# MSP-ISO_Rev1_0.net
KiCad netlist of a schematic drawn in Altium Designer
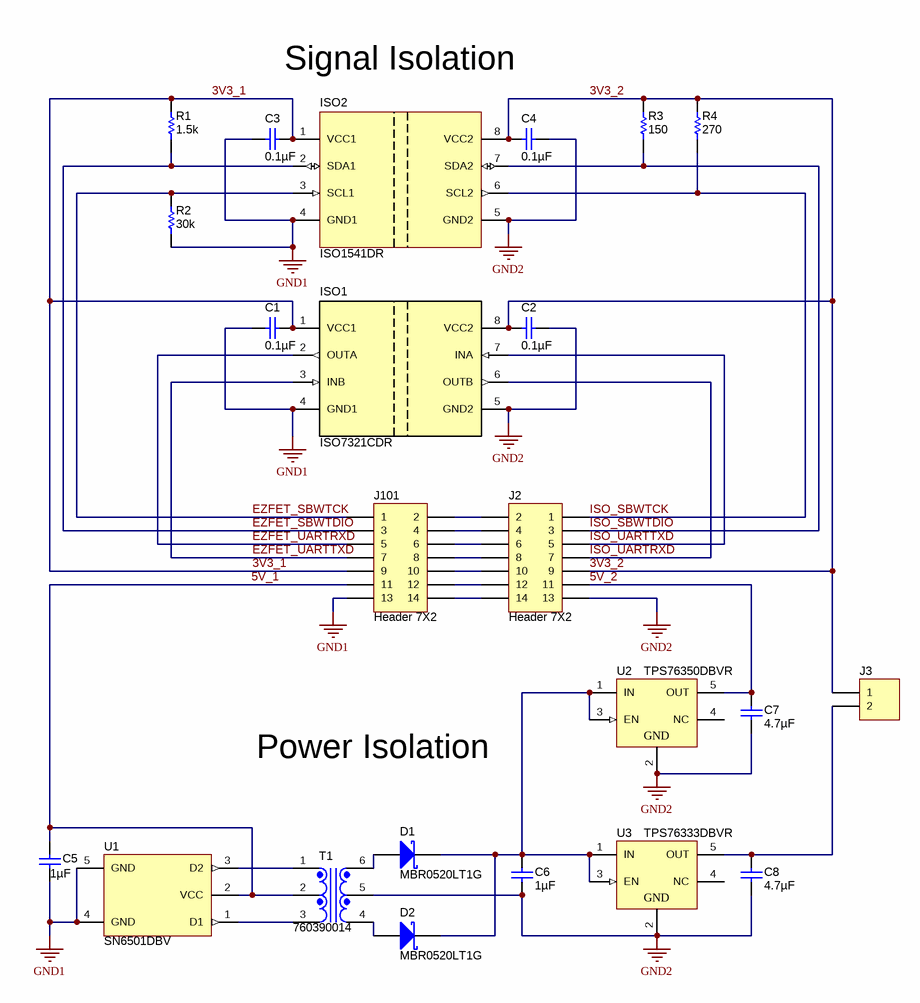
[diagram p0: MSP-ISO_Rev1_0.SchDoc]

(export (version "E")
  (design (tool "Eeschema 10.0.6"))
  (components
    (comp (ref "C1")
      (value "0603YC104JAT2A")
      (footprint "0603")
      (description "CAP, CERM, 0.1 µF, 16 V, +/- 5%, X7R, 0603")
      (fields
        (field (name "VALUEDISPLAYED") "0.1µF")
        (field (name "MANUFACTURER") "AVX")
        (field (name "PUBLISHER") "Texas Instruments")
      )
      (libsource (lib "Capacitor_Ceramic") (part "0603YC104JAT2A"))
    )
    (comp (ref "C2")
      (value "0603YC104JAT2A")
      (footprint "0603")
      (description "CAP, CERM, 0.1 µF, 16 V, +/- 5%, X7R, 0603")
      (fields
        (field (name "VALUEDISPLAYED") "0.1µF")
        (field (name "MANUFACTURER") "AVX")
        (field (name "PUBLISHER") "Texas Instruments")
      )
      (libsource (lib "Capacitor_Ceramic") (part "0603YC104JAT2A"))
    )
    (comp (ref "C3")
      (value "0603YC104JAT2A")
      (footprint "0603")
      (description "CAP, CERM, 0.1 µF, 16 V, +/- 5%, X7R, 0603")
      (fields
        (field (name "VALUEDISPLAYED") "0.1µF")
        (field (name "MANUFACTURER") "AVX")
        (field (name "PUBLISHER") "Texas Instruments")
      )
      (libsource (lib "Capacitor_Ceramic") (part "0603YC104JAT2A"))
    )
    (comp (ref "C4")
      (value "0603YC104JAT2A")
      (footprint "0603")
      (description "CAP, CERM, 0.1 µF, 16 V, +/- 5%, X7R, 0603")
      (fields
        (field (name "VALUEDISPLAYED") "0.1µF")
        (field (name "MANUFACTURER") "AVX")
        (field (name "PUBLISHER") "Texas Instruments")
      )
      (libsource (lib "Capacitor_Ceramic") (part "0603YC104JAT2A"))
    )
    (comp (ref "C5")
      (value "C1608X7R1C105K")
      (footprint "0603")
      (description "CAP, CERM, 1 µF, 16 V, +/- 10%, X7R, 0603")
      (fields
        (field (name "VALUEDISPLAYED") "1µF")
        (field (name "MANUFACTURER") "TDK")
        (field (name "PUBLISHER") "Texas Instruments")
      )
      (libsource (lib "Capacitor_Ceramic") (part "C1608X7R1C105K"))
    )
    (comp (ref "C6")
      (value "C1608X7R1C105K")
      (footprint "0603")
      (description "CAP, CERM, 1 µF, 16 V, +/- 10%, X7R, 0603")
      (fields
        (field (name "VALUEDISPLAYED") "1µF")
        (field (name "MANUFACTURER") "TDK")
        (field (name "PUBLISHER") "Texas Instruments")
      )
      (libsource (lib "Capacitor_Ceramic") (part "C1608X7R1C105K"))
    )
    (comp (ref "C7")
      (value "C1608X5R0J475M")
      (footprint "0603")
      (description "CAP, CERM, 4.7 µF, 6.3 V, +/- 20%, X5R, 0603")
      (fields
        (field (name "VALUEDISPLAYED") "4.7µF")
        (field (name "MANUFACTURER") "TDK")
        (field (name "PUBLISHER") "Texas Instruments")
      )
      (libsource (lib "Capacitor_Ceramic") (part "C1608X5R0J475M"))
    )
    (comp (ref "C8")
      (value "C1608X5R0J475M")
      (footprint "0603")
      (description "CAP, CERM, 4.7 µF, 6.3 V, +/- 20%, X5R, 0603")
      (fields
        (field (name "VALUEDISPLAYED") "4.7µF")
        (field (name "MANUFACTURER") "TDK")
        (field (name "PUBLISHER") "Texas Instruments")
      )
      (libsource (lib "Capacitor_Ceramic") (part "C1608X5R0J475M"))
    )
    (comp (ref "D1")
      (value "MBR0520LT1G")
      (footprint "SOD-123")
      (description "Diode, Schottky, 20 V, 0.5 A, SOD-123")
      (fields (field (name "MANUFACTURER") "ON Semiconductor") (field (name "PUBLISHER") "Texas Instruments"))
      (libsource (lib "Diode") (part "MBR0520LT1G"))
    )
    (comp (ref "D2")
      (value "MBR0520LT1G")
      (footprint "SOD-123")
      (description "Diode, Schottky, 20 V, 0.5 A, SOD-123")
      (fields (field (name "MANUFACTURER") "ON Semiconductor") (field (name "PUBLISHER") "Texas Instruments"))
      (libsource (lib "Diode") (part "MBR0520LT1G"))
    )
    (comp (ref "ISO1")
      (value "ISO7321CDR")
      (footprint "D0008B_N")
      (description "Robust EMC, Low Power, Dual-Channel Digital Isolators, D0008B")
      (fields
        (field (name "ALTERNATE PARTNUMBER") "ISO7321CD")
        (field (name "MANUFACTURER") "Texas Instruments")
        (field (name "SYMBOLCREATOR") "a0411947")
        (field (name "PUBLISHER") "Texas Instruments")
      )
      (libsource (lib "TI_Pre_Release1") (part "ISO7321CDR"))
    )
    (comp (ref "ISO2")
      (value "ISO1541DR")
      (footprint "D0008A_N")
      (description "Low-Power Bidirectional I2C Isolators, D0008A")
      (fields
        (field (name "ALTERNATE PARTNUMBER") "ISO1541D")
        (field (name "MANUFACTURER") "Texas Instruments")
        (field (name "SYMBOLCREATOR") "a0411947")
        (field (name "PUBLISHER") "Texas Instruments")
      )
      (libsource (lib "TI_Pre_Release1") (part "ISO1541DR"))
    )
    (comp (ref "J2")
      (value "Header 7X2")
      (footprint "HDR2X7")
      (description "Header, 7-Pin, Dual row")
      (fields (field (name "PUBLISHER") "Altium Limited"))
      (libsource (lib "Miscellaneous Connectors") (part "Header 7X2"))
    )
    (comp (ref "J3")
      (value "Supply_components")
      (footprint "HDR1X2")
      (description "Header, 2-Pin")
      (fields (field (name "PUBLISHER") "Altium Limited"))
      (libsource (lib "Miscellaneous Connectors") (part "Header 2"))
    )
    (comp (ref "J101")
      (value "Header 7X2")
      (footprint "HDR2X7")
      (description "Header, 7-Pin, Dual row")
      (fields (field (name "PUBLISHER") "Altium Limited"))
      (libsource (lib "") (part "Header 7X2_1"))
    )
    (comp (ref "R1")
      (value "CRCW04021K50JNED")
      (footprint "0402")
      (description "RES, 1.5 k, 5%, 0.063 W, 0402")
      (fields
        (field (name "VALUEDISPLAYED") "1.5k")
        (field (name "MANUFACTURER") "Vishay-Dale")
        (field (name "PUBLISHER") "Texas Instruments")
      )
      (libsource (lib "Resistor_0402") (part "CRCW04021K50JNED"))
    )
    (comp (ref "R2")
      (value "CRCW040230K0JNED")
      (footprint "0402")
      (description "RES, 30 k, 5%, 0.063 W, 0402")
      (fields
        (field (name "VALUEDISPLAYED") "30k")
        (field (name "MANUFACTURER") "Vishay-Dale")
        (field (name "PUBLISHER") "Texas Instruments")
      )
      (libsource (lib "Resistor_0402") (part "CRCW040230K0JNED"))
    )
    (comp (ref "R3")
      (value "CRCW0402150RJNED")
      (footprint "0402")
      (description "RES, 150, 5%, 0.063 W, 0402")
      (fields
        (field (name "VALUEDISPLAYED") "150")
        (field (name "MANUFACTURER") "Vishay-Dale")
        (field (name "PUBLISHER") "Texas Instruments")
      )
      (libsource (lib "Resistor_0402") (part "CRCW0402150RJNED"))
    )
    (comp (ref "R4")
      (value "CRCW0402270RJNED")
      (footprint "0402")
      (description "RES, 270, 5%, 0.063 W, 0402")
      (fields
        (field (name "VALUEDISPLAYED") "270")
        (field (name "MANUFACTURER") "Vishay-Dale")
        (field (name "PUBLISHER") "Texas Instruments")
      )
      (libsource (lib "Resistor_0402") (part "CRCW0402270RJNED"))
    )
    (comp (ref "T1")
      (value "760390014")
      (footprint "Wurth_760390013")
      (description "Transformer, 475uH, SMT")
      (fields
        (field (name "MANUFACTURER") "Wurth Elektronik eiSos")
        (field (name "SYMBOLCREATOR") "a0799628")
        (field (name "PUBLISHER") "Texas Instruments")
      )
      (libsource (lib "Transformers") (part "760390014"))
    )
    (comp (ref "U1")
      (value "SN6501DBV")
      (footprint "DBV0005A_N")
      (description "Transformer Driver for Isolated Power Supplies, DBV0005A")
      (fields
        (field (name "MANUFACTURER") "Texas Instruments")
        (field (name "SYMBOLCREATOR") "a0411947")
        (field (name "PUBLISHER") "Texas Instruments")
      )
      (libsource (lib "TI_Pre_Release") (part "SN6501DBV"))
    )
    (comp (ref "U2")
      (value "TPS76350DBVR")
      (footprint "DBV0005A_N")
      (fields
        (field (name "MANUFACTURER") "Texas Instruments")
        (field (name "ALTERNATE PARTNUMBER") "Equivalent")
      )
      (libsource (lib "TI Power Management Linear Regulator Single Channel LDO (0-350mA)") (part "TPS76350DBVR"))
    )
    (comp (ref "U3")
      (value "TPS76333DBVR")
      (footprint "DBV0005A_N")
      (fields
        (field (name "MANUFACTURER") "Texas Instruments")
        (field (name "ALTERNATE PARTNUMBER") "Equivalent")
      )
      (libsource (lib "TI Power Management Linear Regulator Single Channel LDO (0-350mA)") (part "TPS76333DBVR"))
    )
  )
  (nets
    (net (code "1") (name "/3V3_1") (class "Default")
      (node (ref "C1") (pin "1") (pinfunction "1_1") (pintype "passive"))
      (node (ref "C3") (pin "1") (pinfunction "1_1") (pintype "passive"))
      (node (ref "ISO1") (pin "1") (pinfunction "VCC1_1") (pintype "power_in"))
      (node (ref "ISO2") (pin "1") (pinfunction "VCC1_1") (pintype "power_in"))
      (node (ref "J101") (pin "9") (pinfunction "9_9") (pintype "passive"))
      (node (ref "R1") (pin "2") (pinfunction "2_2") (pintype "passive"))
    )
    (net (code "2") (name "/3V3_2") (class "Default")
      (node (ref "C2") (pin "1") (pinfunction "1_1") (pintype "passive"))
      (node (ref "C4") (pin "1") (pinfunction "1_1") (pintype "passive"))
      (node (ref "ISO1") (pin "8") (pinfunction "VCC2_8") (pintype "power_in"))
      (node (ref "ISO2") (pin "8") (pinfunction "VCC2_8") (pintype "power_in"))
      (node (ref "J2") (pin "9") (pinfunction "9_9") (pintype "passive"))
      (node (ref "J3") (pin "1") (pinfunction "1_1") (pintype "passive"))
      (node (ref "R3") (pin "2") (pinfunction "2_2") (pintype "passive"))
      (node (ref "R4") (pin "2") (pinfunction "2_2") (pintype "passive"))
    )
    (net (code "3") (name "/5V_1") (class "Default")
      (node (ref "C5") (pin "1") (pinfunction "1_1") (pintype "passive"))
      (node (ref "J101") (pin "11") (pinfunction "11_11") (pintype "passive"))
      (node (ref "T1") (pin "2") (pinfunction "2_2") (pintype "passive"))
      (node (ref "U1") (pin "2") (pinfunction "VCC_2") (pintype "power_in"))
    )
    (net (code "4") (name "/5V_2") (class "Default")
      (node (ref "C7") (pin "1") (pinfunction "1_1") (pintype "passive"))
      (node (ref "J2") (pin "11") (pinfunction "11_11") (pintype "passive"))
      (node (ref "U2") (pin "5") (pinfunction "OUT_5") (pintype "power_in"))
    )
    (net (code "5") (name "/EZFET_SBWTCK") (class "Default")
      (node (ref "ISO2") (pin "3") (pinfunction "SCL1_3") (pintype "input"))
      (node (ref "J101") (pin "1") (pinfunction "1_1") (pintype "passive"))
      (node (ref "R2") (pin "2") (pinfunction "2_2") (pintype "passive"))
    )
    (net (code "6") (name "/EZFET_SBWTDIO") (class "Default")
      (node (ref "ISO2") (pin "2") (pinfunction "SDA1_2") (pintype "bidirectional"))
      (node (ref "J101") (pin "3") (pinfunction "3_3") (pintype "passive"))
      (node (ref "R1") (pin "1") (pinfunction "1_1") (pintype "passive"))
    )
    (net (code "7") (name "/EZFET_UARTRXD") (class "Default")
      (node (ref "ISO1") (pin "2") (pinfunction "OUTA_2") (pintype "output"))
      (node (ref "J101") (pin "5") (pinfunction "5_5") (pintype "passive"))
    )
    (net (code "8") (name "/EZFET_UARTTXD") (class "Default")
      (node (ref "ISO1") (pin "3") (pinfunction "INB_3") (pintype "input"))
      (node (ref "J101") (pin "7") (pinfunction "7_7") (pintype "passive"))
    )
    (net (code "9") (name "/ISO_SBWTCK") (class "Default")
      (node (ref "ISO2") (pin "6") (pinfunction "SCL2_6") (pintype "output"))
      (node (ref "J2") (pin "1") (pinfunction "1_1") (pintype "passive"))
      (node (ref "R4") (pin "1") (pinfunction "1_1") (pintype "passive"))
    )
    (net (code "10") (name "/ISO_SBWTDIO") (class "Default")
      (node (ref "ISO2") (pin "7") (pinfunction "SDA2_7") (pintype "bidirectional"))
      (node (ref "J2") (pin "3") (pinfunction "3_3") (pintype "passive"))
      (node (ref "R3") (pin "1") (pinfunction "1_1") (pintype "passive"))
    )
    (net (code "11") (name "/ISO_UARTRXD") (class "Default")
      (node (ref "ISO1") (pin "6") (pinfunction "OUTB_6") (pintype "output"))
      (node (ref "J2") (pin "7") (pinfunction "7_7") (pintype "passive"))
    )
    (net (code "12") (name "/ISO_UARTTXD") (class "Default")
      (node (ref "ISO1") (pin "7") (pinfunction "INA_7") (pintype "input"))
      (node (ref "J2") (pin "5") (pinfunction "5_5") (pintype "passive"))
    )
    (net (code "13") (name "GND1") (class "Default")
      (node (ref "C1") (pin "2") (pinfunction "2_2") (pintype "passive"))
      (node (ref "C3") (pin "2") (pinfunction "2_2") (pintype "passive"))
      (node (ref "C5") (pin "2") (pinfunction "2_2") (pintype "passive"))
      (node (ref "ISO1") (pin "4") (pinfunction "GND1_4") (pintype "power_in"))
      (node (ref "ISO2") (pin "4") (pinfunction "GND1_4") (pintype "power_in"))
      (node (ref "J101") (pin "13") (pinfunction "13_13") (pintype "passive"))
      (node (ref "R2") (pin "1") (pinfunction "1_1") (pintype "passive"))
      (node (ref "U1") (pin "4") (pinfunction "GND_4") (pintype "power_in"))
      (node (ref "U1") (pin "5") (pinfunction "GND_5") (pintype "power_in"))
    )
    (net (code "14") (name "GND2") (class "Default")
      (node (ref "C2") (pin "2") (pinfunction "2_2") (pintype "passive"))
      (node (ref "C4") (pin "2") (pinfunction "2_2") (pintype "passive"))
      (node (ref "C6") (pin "2") (pinfunction "2_2") (pintype "passive"))
      (node (ref "C7") (pin "2") (pinfunction "2_2") (pintype "passive"))
      (node (ref "C8") (pin "2") (pinfunction "2_2") (pintype "passive"))
      (node (ref "ISO1") (pin "5") (pinfunction "GND2_5") (pintype "passive"))
      (node (ref "ISO2") (pin "5") (pinfunction "GND2_5") (pintype "power_in"))
      (node (ref "J2") (pin "13") (pinfunction "13_13") (pintype "passive"))
      (node (ref "T1") (pin "5") (pinfunction "5_5") (pintype "passive"))
      (node (ref "U2") (pin "2") (pinfunction "GND_2") (pintype "power_in"))
      (node (ref "U3") (pin "2") (pinfunction "GND_2") (pintype "power_in"))
    )
    (net (code "15") (name "Net-(D1-A)") (class "Default")
      (node (ref "D1") (pin "2") (pinfunction "A_2") (pintype "passive"))
      (node (ref "T1") (pin "6") (pinfunction "6_6") (pintype "passive"))
    )
    (net (code "16") (name "Net-(D1-K)") (class "Default")
      (node (ref "C6") (pin "1") (pinfunction "1_1") (pintype "passive"))
      (node (ref "D1") (pin "1") (pinfunction "K_1") (pintype "passive"))
      (node (ref "D2") (pin "1") (pinfunction "K_1") (pintype "passive"))
      (node (ref "U2") (pin "1") (pinfunction "IN_1") (pintype "power_in"))
      (node (ref "U2") (pin "3") (pinfunction "EN_3") (pintype "input"))
      (node (ref "U3") (pin "1") (pinfunction "IN_1") (pintype "power_in"))
      (node (ref "U3") (pin "3") (pinfunction "EN_3") (pintype "input"))
    )
    (net (code "17") (name "Net-(D2-A)") (class "Default")
      (node (ref "D2") (pin "2") (pinfunction "A_2") (pintype "passive"))
      (node (ref "T1") (pin "4") (pinfunction "4_4") (pintype "passive"))
    )
    (net (code "18") (name "Net-(J101-Pad2)") (class "Default")
      (node (ref "J101") (pin "2") (pinfunction "2_2") (pintype "passive"))
      (node (ref "J2") (pin "2") (pinfunction "2_2") (pintype "passive"))
    )
    (net (code "19") (name "Net-(J101-Pad4)") (class "Default")
      (node (ref "J101") (pin "4") (pinfunction "4_4") (pintype "passive"))
      (node (ref "J2") (pin "4") (pinfunction "4_4") (pintype "passive"))
    )
    (net (code "20") (name "Net-(J101-Pad6)") (class "Default")
      (node (ref "J101") (pin "6") (pinfunction "6_6") (pintype "passive"))
      (node (ref "J2") (pin "6") (pinfunction "6_6") (pintype "passive"))
    )
    (net (code "21") (name "Net-(J101-Pad8)") (class "Default")
      (node (ref "J101") (pin "8") (pinfunction "8_8") (pintype "passive"))
      (node (ref "J2") (pin "8") (pinfunction "8_8") (pintype "passive"))
    )
    (net (code "22") (name "Net-(J101-Pad10)") (class "Default")
      (node (ref "J101") (pin "10") (pinfunction "10_10") (pintype "passive"))
      (node (ref "J2") (pin "10") (pinfunction "10_10") (pintype "passive"))
    )
    (net (code "23") (name "Net-(J101-Pad12)") (class "Default")
      (node (ref "J101") (pin "12") (pinfunction "12_12") (pintype "passive"))
      (node (ref "J2") (pin "12") (pinfunction "12_12") (pintype "passive"))
    )
    (net (code "24") (name "Net-(J101-Pad14)") (class "Default")
      (node (ref "J101") (pin "14") (pinfunction "14_14") (pintype "passive"))
      (node (ref "J2") (pin "14") (pinfunction "14_14") (pintype "passive"))
    )
    (net (code "25") (name "Net-(U1-D1)") (class "Default")
      (node (ref "T1") (pin "3") (pinfunction "3_3") (pintype "passive"))
      (node (ref "U1") (pin "1") (pinfunction "D1_1") (pintype "output"))
    )
    (net (code "26") (name "Net-(U1-D2)") (class "Default")
      (node (ref "T1") (pin "1") (pinfunction "1_1") (pintype "passive"))
      (node (ref "U1") (pin "3") (pinfunction "D2_3") (pintype "output"))
    )
    (net (code "27") (name "Net-(U3-OUT)") (class "Default")
      (node (ref "C8") (pin "1") (pinfunction "1_1") (pintype "passive"))
      (node (ref "J3") (pin "2") (pinfunction "2_2") (pintype "passive"))
      (node (ref "U3") (pin "5") (pinfunction "OUT_5") (pintype "power_in"))
    )
    (net (code "28") (name "unconnected-(U2-NC-Pad4)") (class "Default")
      (node (ref "U2") (pin "4") (pinfunction "NC_4") (pintype "passive"))
    )
    (net (code "29") (name "unconnected-(U3-NC-Pad4)") (class "Default")
      (node (ref "U3") (pin "4") (pinfunction "NC_4") (pintype "passive"))
    )
  )
)
